# KGM_9DOF_v2_0.net
KiCad netlist of a schematic drawn in EAGLE
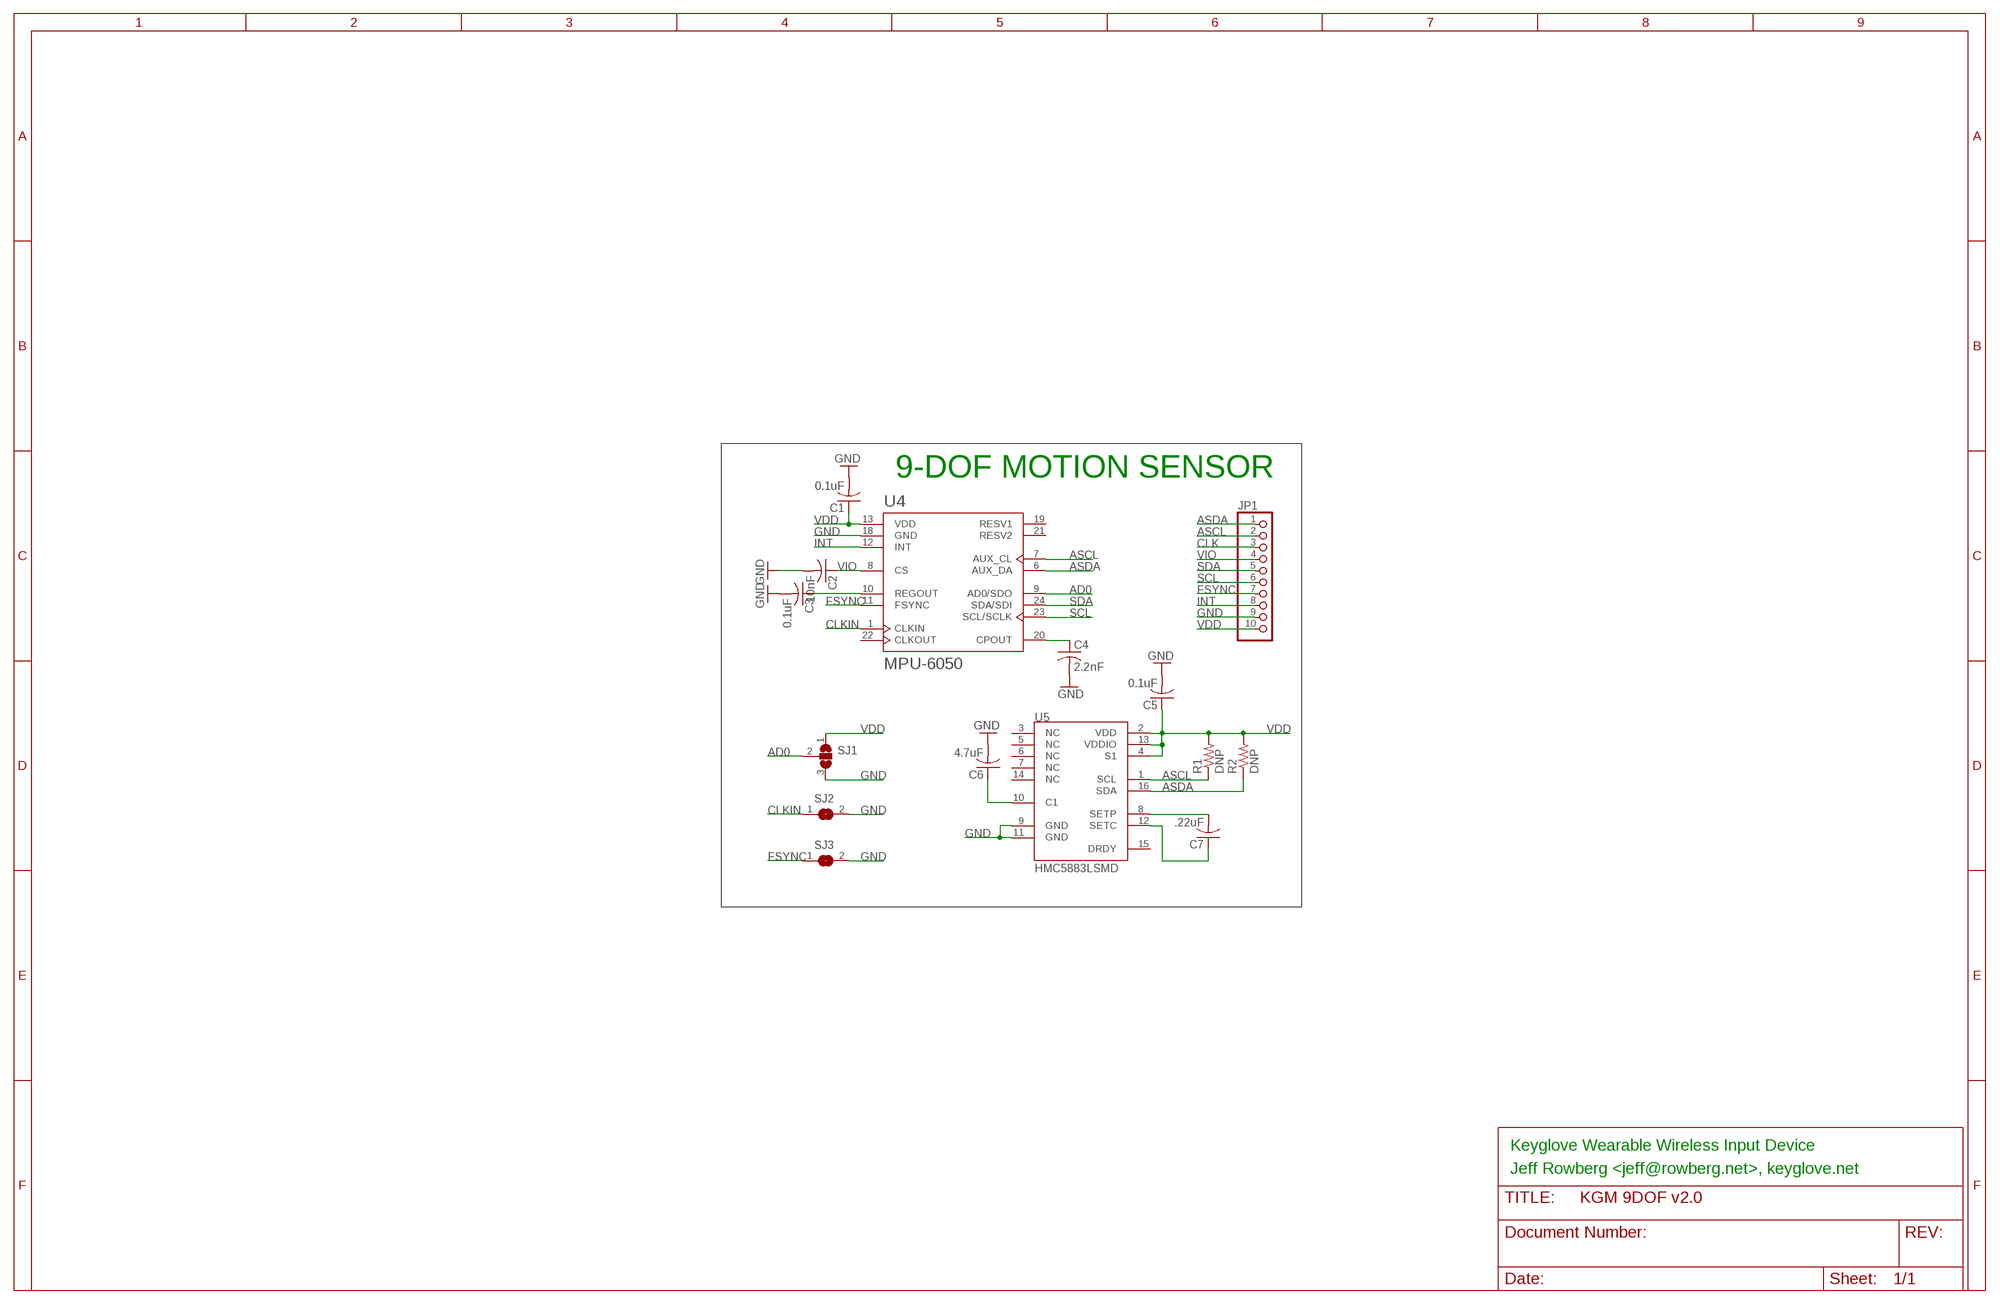
[diagram p0: schematic, sheet 1]

(export (version "E")
  (design (tool "Eeschema 10.0.6"))
  (components
    (comp (ref "C1")
      (value "0.1uF")
      (footprint "eagle-import:C0603")
      (libsource (lib "eagle-import") (part "C-USC0603"))
    )
    (comp (ref "C2")
      (value "10nF")
      (footprint "eagle-import:C0603")
      (libsource (lib "eagle-import") (part "C-USC0603"))
    )
    (comp (ref "C3")
      (value "0.1uF")
      (footprint "eagle-import:C0603")
      (libsource (lib "eagle-import") (part "C-USC0603"))
    )
    (comp (ref "C4")
      (value "2.2nF")
      (footprint "eagle-import:C0603")
      (libsource (lib "eagle-import") (part "C-USC0603"))
    )
    (comp (ref "C5")
      (value "0.1uF")
      (footprint "eagle-import:C0603")
      (libsource (lib "eagle-import") (part "C-USC0603"))
    )
    (comp (ref "C6")
      (value "4.7uF")
      (footprint "eagle-import:C0603")
      (libsource (lib "eagle-import") (part "C-USC0603"))
    )
    (comp (ref "C7")
      (value ".22uF")
      (footprint "eagle-import:C0603")
      (libsource (lib "eagle-import") (part "C-USC0603"))
    )
    (comp (ref "JP1")
      (value "PINHD-1X10")
      (footprint "eagle-import:1X10")
      (libsource (lib "eagle-import") (part "PINHD-1X10"))
    )
    (comp (ref "R1")
      (value "DNP")
      (footprint "eagle-import:R0603")
      (libsource (lib "eagle-import") (part "R-US_R0603"))
    )
    (comp (ref "R2")
      (value "DNP")
      (footprint "eagle-import:R0603")
      (libsource (lib "eagle-import") (part "R-US_R0603"))
    )
    (comp (ref "SJ1")
      (value "SJ2W")
      (footprint "eagle-import:SJ_2")
      (libsource (lib "eagle-import") (part "SJ2W"))
    )
    (comp (ref "SJ2") (value "SJ") (footprint "eagle-import:SJ") (libsource (lib "eagle-import") (part "SJ")))
    (comp (ref "SJ3") (value "SJ") (footprint "eagle-import:SJ") (libsource (lib "eagle-import") (part "SJ")))
    (comp (ref "U4")
      (value "MPU-6050")
      (footprint "eagle-import:QFN24MPU")
      (libsource (lib "eagle-import") (part "MPU-6000"))
    )
    (comp (ref "U5")
      (value "HMC5883LSMD")
      (footprint "eagle-import:16LPCC")
      (libsource (lib "eagle-import") (part "HMC5883LSMD"))
    )
  )
  (nets
    (net (code "1") (name "/AD0") (class "Default")
      (node (ref "SJ1") (pin "2") (pinfunction "2_2") (pintype "passive"))
      (node (ref "U4") (pin "9") (pinfunction "AD0/SDO_9") (pintype "bidirectional"))
    )
    (net (code "2") (name "/ASCL") (class "Default")
      (node (ref "JP1") (pin "2") (pinfunction "2_2") (pintype "passive"))
      (node (ref "R1") (pin "1") (pinfunction "1_1") (pintype "passive"))
      (node (ref "U4") (pin "7") (pinfunction "AUX_CL_7") (pintype "bidirectional"))
      (node (ref "U5") (pin "1") (pinfunction "SCL_1") (pintype "bidirectional"))
    )
    (net (code "3") (name "/ASDA") (class "Default")
      (node (ref "JP1") (pin "1") (pinfunction "1_1") (pintype "passive"))
      (node (ref "R2") (pin "1") (pinfunction "1_1") (pintype "passive"))
      (node (ref "U4") (pin "6") (pinfunction "AUX_DA_6") (pintype "bidirectional"))
      (node (ref "U5") (pin "16") (pinfunction "SDA_16") (pintype "bidirectional"))
    )
    (net (code "4") (name "/CLK") (class "Default")
      (node (ref "JP1") (pin "3") (pinfunction "3_3") (pintype "passive"))
    )
    (net (code "5") (name "/CLKIN") (class "Default")
      (node (ref "SJ2") (pin "1") (pinfunction "1_1") (pintype "passive"))
      (node (ref "U4") (pin "1") (pinfunction "CLKIN_1") (pintype "input"))
    )
    (net (code "6") (name "/FSYNC") (class "Default")
      (node (ref "JP1") (pin "7") (pinfunction "7_7") (pintype "passive"))
      (node (ref "SJ3") (pin "1") (pinfunction "1_1") (pintype "passive"))
      (node (ref "U4") (pin "11") (pinfunction "FSYNC_11") (pintype "input"))
    )
    (net (code "7") (name "/INT") (class "Default")
      (node (ref "JP1") (pin "8") (pinfunction "8_8") (pintype "passive"))
      (node (ref "U4") (pin "12") (pinfunction "INT_12") (pintype "bidirectional"))
    )
    (net (code "8") (name "/SCL") (class "Default")
      (node (ref "JP1") (pin "6") (pinfunction "6_6") (pintype "passive"))
      (node (ref "U4") (pin "23") (pinfunction "SCL/SCLK_23") (pintype "input"))
    )
    (net (code "9") (name "/SDA") (class "Default")
      (node (ref "JP1") (pin "5") (pinfunction "5_5") (pintype "passive"))
      (node (ref "U4") (pin "24") (pinfunction "SDA/SDI_24") (pintype "bidirectional"))
    )
    (net (code "10") (name "/VDD") (class "Default")
      (node (ref "C1") (pin "1") (pinfunction "1_1") (pintype "passive"))
      (node (ref "C5") (pin "1") (pinfunction "1_1") (pintype "passive"))
      (node (ref "JP1") (pin "10") (pinfunction "10_10") (pintype "passive"))
      (node (ref "R1") (pin "2") (pinfunction "2_2") (pintype "passive"))
      (node (ref "R2") (pin "2") (pinfunction "2_2") (pintype "passive"))
      (node (ref "SJ1") (pin "1") (pinfunction "1_1") (pintype "passive"))
      (node (ref "U4") (pin "13") (pinfunction "VDD_13") (pintype "power_in"))
      (node (ref "U5") (pin "13") (pinfunction "VDDIO_13") (pintype "bidirectional"))
      (node (ref "U5") (pin "2") (pinfunction "VDD_2") (pintype "bidirectional"))
      (node (ref "U5") (pin "4") (pinfunction "S1_4") (pintype "bidirectional"))
    )
    (net (code "11") (name "/VIO") (class "Default")
      (node (ref "C2") (pin "1") (pinfunction "1_1") (pintype "passive"))
      (node (ref "JP1") (pin "4") (pinfunction "4_4") (pintype "passive"))
      (node (ref "U4") (pin "8") (pinfunction "CS_8") (pintype "input"))
    )
    (net (code "12") (name "GND") (class "Default")
      (node (ref "C1") (pin "2") (pinfunction "2_2") (pintype "passive"))
      (node (ref "C2") (pin "2") (pinfunction "2_2") (pintype "passive"))
      (node (ref "C3") (pin "2") (pinfunction "2_2") (pintype "passive"))
      (node (ref "C4") (pin "2") (pinfunction "2_2") (pintype "passive"))
      (node (ref "C5") (pin "2") (pinfunction "2_2") (pintype "passive"))
      (node (ref "C6") (pin "2") (pinfunction "2_2") (pintype "passive"))
      (node (ref "JP1") (pin "9") (pinfunction "9_9") (pintype "passive"))
      (node (ref "SJ1") (pin "3") (pinfunction "3_3") (pintype "passive"))
      (node (ref "SJ2") (pin "2") (pinfunction "2_2") (pintype "passive"))
      (node (ref "SJ3") (pin "2") (pinfunction "2_2") (pintype "passive"))
      (node (ref "U4") (pin "18") (pinfunction "GND_18") (pintype "power_in"))
      (node (ref "U5") (pin "11") (pinfunction "GND_11") (pintype "bidirectional"))
      (node (ref "U5") (pin "9") (pinfunction "GND_9") (pintype "bidirectional"))
    )
    (net (code "13") (name "Net-(U4-CPOUT)") (class "Default")
      (node (ref "C4") (pin "1") (pinfunction "1_1") (pintype "passive"))
      (node (ref "U4") (pin "20") (pinfunction "CPOUT_20") (pintype "output"))
    )
    (net (code "14") (name "Net-(U4-REGOUT)") (class "Default")
      (node (ref "C3") (pin "1") (pinfunction "1_1") (pintype "passive"))
      (node (ref "U4") (pin "10") (pinfunction "REGOUT_10") (pintype "bidirectional"))
    )
    (net (code "15") (name "Net-(U5-C1)") (class "Default")
      (node (ref "C6") (pin "1") (pinfunction "1_1") (pintype "passive"))
      (node (ref "U5") (pin "10") (pinfunction "C1_10") (pintype "bidirectional"))
    )
    (net (code "16") (name "Net-(U5-SETC)") (class "Default")
      (node (ref "C7") (pin "1") (pinfunction "1_1") (pintype "passive"))
      (node (ref "U5") (pin "12") (pinfunction "SETC_12") (pintype "bidirectional"))
    )
    (net (code "17") (name "Net-(U5-SETP)") (class "Default")
      (node (ref "C7") (pin "2") (pinfunction "2_2") (pintype "passive"))
      (node (ref "U5") (pin "8") (pinfunction "SETP_8") (pintype "bidirectional"))
    )
    (net (code "18") (name "unconnected-(U4-CLKOUT-Pad22)") (class "Default")
      (node (ref "U4") (pin "22") (pinfunction "CLKOUT_22") (pintype "output"))
    )
    (net (code "19") (name "unconnected-(U4-RESV1-Pad19)") (class "Default")
      (node (ref "U4") (pin "19") (pinfunction "RESV1_19") (pintype "bidirectional"))
    )
    (net (code "20") (name "unconnected-(U4-RESV2-Pad21)") (class "Default")
      (node (ref "U4") (pin "21") (pinfunction "RESV2_21") (pintype "bidirectional"))
    )
    (net (code "21") (name "unconnected-(U5-DRDY-Pad15)") (class "Default")
      (node (ref "U5") (pin "15") (pinfunction "DRDY_15") (pintype "bidirectional"))
    )
    (net (code "22") (name "unconnected-(U5-NC-Pad3)") (class "Default")
      (node (ref "U5") (pin "3") (pinfunction "NC_3") (pintype "bidirectional"))
    )
    (net (code "23") (name "unconnected-(U5-NC-Pad5)") (class "Default")
      (node (ref "U5") (pin "5") (pinfunction "NC_5") (pintype "bidirectional"))
    )
    (net (code "24") (name "unconnected-(U5-NC-Pad6)") (class "Default")
      (node (ref "U5") (pin "6") (pinfunction "NC_6") (pintype "bidirectional"))
    )
    (net (code "25") (name "unconnected-(U5-NC-Pad7)") (class "Default")
      (node (ref "U5") (pin "7") (pinfunction "NC_7") (pintype "bidirectional"))
    )
    (net (code "26") (name "unconnected-(U5-NC-Pad14)") (class "Default")
      (node (ref "U5") (pin "14") (pinfunction "NC_14") (pintype "bidirectional"))
    )
  )
)
